# extbrd.net
KiCad netlist of a schematic drawn in EAGLE
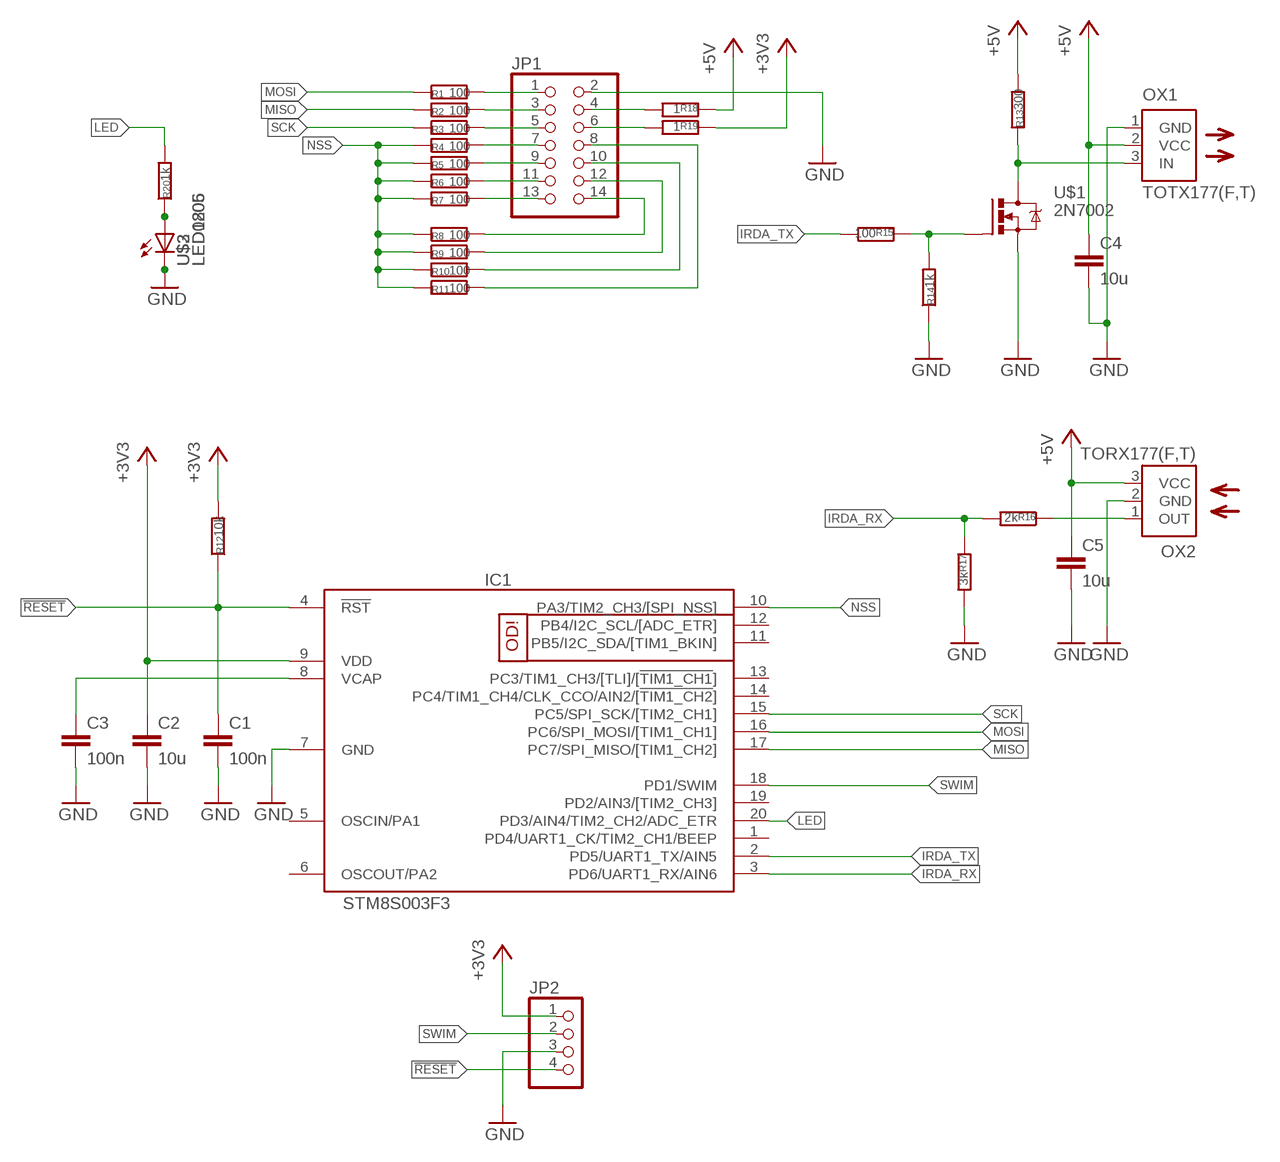
[diagram p0: schematic, sheet 1]

(export (version "E")
  (design (tool "Eeschema 10.0.6"))
  (components
    (comp (ref "C1")
      (value "100n")
      (footprint "eagle-import:C0603")
      (libsource (lib "eagle-import") (part "CC0603"))
    )
    (comp (ref "C2")
      (value "10u")
      (footprint "eagle-import:C0805")
      (libsource (lib "eagle-import") (part "CC0805"))
    )
    (comp (ref "C3")
      (value "100n")
      (footprint "eagle-import:C0603")
      (libsource (lib "eagle-import") (part "CC0603"))
    )
    (comp (ref "C4")
      (value "10u")
      (footprint "eagle-import:C0805")
      (libsource (lib "eagle-import") (part "CC0805"))
    )
    (comp (ref "C5")
      (value "10u")
      (footprint "eagle-import:C0805")
      (libsource (lib "eagle-import") (part "CC0805"))
    )
    (comp (ref "IC1")
      (value "STM8S003F3")
      (footprint "eagle-import:TSSOP20")
      (libsource (lib "eagle-import") (part "STM8S003F3"))
    )
    (comp (ref "JP1")
      (value "PINHD-2X07_2.54-SMD")
      (footprint "eagle-import:2X07SMD")
      (libsource (lib "eagle-import") (part "PINHD-2X07_2.54-SMD"))
    )
    (comp (ref "JP2")
      (value "PINHD-1X04_2.54-SMD")
      (footprint "eagle-import:1X04SMD")
      (libsource (lib "eagle-import") (part "PINHD-1X04_2.54-SMD"))
    )
    (comp (ref "OX1")
      (value "TOTX177(F,T)")
      (footprint "eagle-import:TOTX")
      (libsource (lib "eagle-import") (part "TOTX177(F,T)"))
    )
    (comp (ref "OX2")
      (value "TORX177(F,T)")
      (footprint "eagle-import:TORX")
      (libsource (lib "eagle-import") (part "TORX177(F,T)"))
    )
    (comp (ref "R1")
      (value "100")
      (footprint "eagle-import:0603")
      (libsource (lib "eagle-import") (part "R0603"))
    )
    (comp (ref "R2")
      (value "100")
      (footprint "eagle-import:0603")
      (libsource (lib "eagle-import") (part "R0603"))
    )
    (comp (ref "R3")
      (value "100")
      (footprint "eagle-import:0603")
      (libsource (lib "eagle-import") (part "R0603"))
    )
    (comp (ref "R4")
      (value "100")
      (footprint "eagle-import:0603")
      (libsource (lib "eagle-import") (part "R0603"))
    )
    (comp (ref "R5")
      (value "100")
      (footprint "eagle-import:0603")
      (libsource (lib "eagle-import") (part "R0603"))
    )
    (comp (ref "R6")
      (value "100")
      (footprint "eagle-import:0603")
      (libsource (lib "eagle-import") (part "R0603"))
    )
    (comp (ref "R7")
      (value "100")
      (footprint "eagle-import:0603")
      (libsource (lib "eagle-import") (part "R0603"))
    )
    (comp (ref "R8")
      (value "100")
      (footprint "eagle-import:0603")
      (libsource (lib "eagle-import") (part "R0603"))
    )
    (comp (ref "R9")
      (value "100")
      (footprint "eagle-import:0603")
      (libsource (lib "eagle-import") (part "R0603"))
    )
    (comp (ref "R10")
      (value "100")
      (footprint "eagle-import:0603")
      (libsource (lib "eagle-import") (part "R0603"))
    )
    (comp (ref "R11")
      (value "100")
      (footprint "eagle-import:0603")
      (libsource (lib "eagle-import") (part "R0603"))
    )
    (comp (ref "R12")
      (value "10k")
      (footprint "eagle-import:0603")
      (libsource (lib "eagle-import") (part "R0603"))
    )
    (comp (ref "R13")
      (value "300")
      (footprint "eagle-import:0603")
      (libsource (lib "eagle-import") (part "R0603"))
    )
    (comp (ref "R14")
      (value "1k")
      (footprint "eagle-import:0603")
      (libsource (lib "eagle-import") (part "R0603"))
    )
    (comp (ref "R15")
      (value "100")
      (footprint "eagle-import:0603")
      (libsource (lib "eagle-import") (part "R0603"))
    )
    (comp (ref "R16")
      (value "2k")
      (footprint "eagle-import:0603")
      (libsource (lib "eagle-import") (part "R0603"))
    )
    (comp (ref "R17")
      (value "3k")
      (footprint "eagle-import:0603")
      (libsource (lib "eagle-import") (part "R0603"))
    )
    (comp (ref "R18")
      (value "1")
      (footprint "eagle-import:0603")
      (libsource (lib "eagle-import") (part "R0603"))
    )
    (comp (ref "R19")
      (value "1")
      (footprint "eagle-import:0603")
      (libsource (lib "eagle-import") (part "R0603"))
    )
    (comp (ref "R20")
      (value "1k")
      (footprint "eagle-import:0603")
      (libsource (lib "eagle-import") (part "R0603"))
    )
    (comp (ref "U$1")
      (value "2N7002")
      (footprint "eagle-import:SOT23")
      (libsource (lib "eagle-import") (part "2N7002"))
    )
    (comp (ref "U$2")
      (value "LED0805")
      (footprint "eagle-import:0805-LED")
      (libsource (lib "eagle-import") (part "LED0805"))
    )
    (comp (ref "U$3")
      (value "LED1206")
      (footprint "eagle-import:1206-LED")
      (libsource (lib "eagle-import") (part "LED1206"))
    )
  )
  (nets
    (net (code "1") (name "+3V3") (class "Default")
      (node (ref "C2") (pin "1") (pinfunction "1_1") (pintype "passive"))
      (node (ref "IC1") (pin "9") (pinfunction "VDD_9") (pintype "power_in"))
      (node (ref "JP2") (pin "1") (pinfunction "1_1") (pintype "passive"))
      (node (ref "R12") (pin "2") (pinfunction "2_2") (pintype "passive"))
      (node (ref "R19") (pin "1") (pinfunction "1_1") (pintype "passive"))
    )
    (net (code "2") (name "+5V") (class "Default")
      (node (ref "C4") (pin "1") (pinfunction "1_1") (pintype "passive"))
      (node (ref "C5") (pin "1") (pinfunction "1_1") (pintype "passive"))
      (node (ref "OX1") (pin "2") (pinfunction "VCC_2") (pintype "power_in"))
      (node (ref "OX2") (pin "3") (pinfunction "VCC_3") (pintype "power_in"))
      (node (ref "R13") (pin "2") (pinfunction "2_2") (pintype "passive"))
      (node (ref "R18") (pin "1") (pinfunction "1_1") (pintype "passive"))
    )
    (net (code "3") (name "/~{RESET}") (class "Default")
      (node (ref "C1") (pin "1") (pinfunction "1_1") (pintype "passive"))
      (node (ref "IC1") (pin "4") (pinfunction "~{RST}_4") (pintype "input"))
      (node (ref "JP2") (pin "4") (pinfunction "4_4") (pintype "passive"))
      (node (ref "R12") (pin "1") (pinfunction "1_1") (pintype "passive"))
    )
    (net (code "4") (name "GND") (class "Default")
      (node (ref "C1") (pin "2") (pinfunction "2_2") (pintype "passive"))
      (node (ref "C2") (pin "2") (pinfunction "2_2") (pintype "passive"))
      (node (ref "C3") (pin "2") (pinfunction "2_2") (pintype "passive"))
      (node (ref "C4") (pin "2") (pinfunction "2_2") (pintype "passive"))
      (node (ref "C5") (pin "2") (pinfunction "2_2") (pintype "passive"))
      (node (ref "IC1") (pin "7") (pinfunction "GND_7") (pintype "power_in"))
      (node (ref "JP1") (pin "2") (pinfunction "2_2") (pintype "passive"))
      (node (ref "JP2") (pin "3") (pinfunction "3_3") (pintype "passive"))
      (node (ref "OX1") (pin "1") (pinfunction "GND_1") (pintype "power_in"))
      (node (ref "OX2") (pin "2") (pinfunction "GND_2") (pintype "power_in"))
      (node (ref "R14") (pin "1") (pinfunction "1_1") (pintype "passive"))
      (node (ref "R17") (pin "2") (pinfunction "2_2") (pintype "passive"))
      (node (ref "U$1") (pin "2") (pinfunction "S_2") (pintype "passive"))
      (node (ref "U$2") (pin "C") (pinfunction "C_C") (pintype "passive"))
      (node (ref "U$3") (pin "C") (pinfunction "C_C") (pintype "passive"))
    )
    (net (code "5") (name "IRDA_RX") (class "Default")
      (node (ref "IC1") (pin "3") (pinfunction "PD6/UART1_RX/AIN6_3") (pintype "bidirectional"))
      (node (ref "R16") (pin "2") (pinfunction "2_2") (pintype "passive"))
      (node (ref "R17") (pin "1") (pinfunction "1_1") (pintype "passive"))
    )
    (net (code "6") (name "IRDA_TX") (class "Default")
      (node (ref "IC1") (pin "2") (pinfunction "PD5/UART1_TX/AIN5_2") (pintype "bidirectional"))
      (node (ref "R15") (pin "2") (pinfunction "2_2") (pintype "passive"))
    )
    (net (code "7") (name "LED") (class "Default")
      (node (ref "IC1") (pin "20") (pinfunction "PD3/AIN4/TIM2_CH2/ADC_ETR_20") (pintype "bidirectional"))
      (node (ref "R20") (pin "2") (pinfunction "2_2") (pintype "passive"))
    )
    (net (code "8") (name "MISO") (class "Default")
      (node (ref "IC1") (pin "17") (pinfunction "PC7/SPI_MISO/[TIM1_CH2]_17") (pintype "bidirectional"))
      (node (ref "R2") (pin "1") (pinfunction "1_1") (pintype "passive"))
    )
    (net (code "9") (name "MOSI") (class "Default")
      (node (ref "IC1") (pin "16") (pinfunction "PC6/SPI_MOSI/[TIM1_CH1]_16") (pintype "bidirectional"))
      (node (ref "R1") (pin "1") (pinfunction "1_1") (pintype "passive"))
    )
    (net (code "10") (name "NSS") (class "Default")
      (node (ref "IC1") (pin "10") (pinfunction "PA3/TIM2_CH3/[SPI_NSS]_10") (pintype "bidirectional"))
      (node (ref "R10") (pin "1") (pinfunction "1_1") (pintype "passive"))
      (node (ref "R11") (pin "1") (pinfunction "1_1") (pintype "passive"))
      (node (ref "R4") (pin "1") (pinfunction "1_1") (pintype "passive"))
      (node (ref "R5") (pin "1") (pinfunction "1_1") (pintype "passive"))
      (node (ref "R6") (pin "1") (pinfunction "1_1") (pintype "passive"))
      (node (ref "R7") (pin "1") (pinfunction "1_1") (pintype "passive"))
      (node (ref "R8") (pin "1") (pinfunction "1_1") (pintype "passive"))
      (node (ref "R9") (pin "1") (pinfunction "1_1") (pintype "passive"))
    )
    (net (code "11") (name "Net-(IC1-VCAP)") (class "Default")
      (node (ref "C3") (pin "1") (pinfunction "1_1") (pintype "passive"))
      (node (ref "IC1") (pin "8") (pinfunction "VCAP_8") (pintype "power_in"))
    )
    (net (code "12") (name "Net-(JP1-Pad1)") (class "Default")
      (node (ref "JP1") (pin "1") (pinfunction "1_1") (pintype "passive"))
      (node (ref "R1") (pin "2") (pinfunction "2_2") (pintype "passive"))
    )
    (net (code "13") (name "Net-(JP1-Pad3)") (class "Default")
      (node (ref "JP1") (pin "3") (pinfunction "3_3") (pintype "passive"))
      (node (ref "R2") (pin "2") (pinfunction "2_2") (pintype "passive"))
    )
    (net (code "14") (name "Net-(JP1-Pad4)") (class "Default")
      (node (ref "JP1") (pin "4") (pinfunction "4_4") (pintype "passive"))
      (node (ref "R18") (pin "2") (pinfunction "2_2") (pintype "passive"))
    )
    (net (code "15") (name "Net-(JP1-Pad5)") (class "Default")
      (node (ref "JP1") (pin "5") (pinfunction "5_5") (pintype "passive"))
      (node (ref "R3") (pin "2") (pinfunction "2_2") (pintype "passive"))
    )
    (net (code "16") (name "Net-(JP1-Pad6)") (class "Default")
      (node (ref "JP1") (pin "6") (pinfunction "6_6") (pintype "passive"))
      (node (ref "R19") (pin "2") (pinfunction "2_2") (pintype "passive"))
    )
    (net (code "17") (name "Net-(JP1-Pad7)") (class "Default")
      (node (ref "JP1") (pin "7") (pinfunction "7_7") (pintype "passive"))
      (node (ref "R4") (pin "2") (pinfunction "2_2") (pintype "passive"))
    )
    (net (code "18") (name "Net-(JP1-Pad8)") (class "Default")
      (node (ref "JP1") (pin "8") (pinfunction "8_8") (pintype "passive"))
      (node (ref "R11") (pin "2") (pinfunction "2_2") (pintype "passive"))
    )
    (net (code "19") (name "Net-(JP1-Pad9)") (class "Default")
      (node (ref "JP1") (pin "9") (pinfunction "9_9") (pintype "passive"))
      (node (ref "R5") (pin "2") (pinfunction "2_2") (pintype "passive"))
    )
    (net (code "20") (name "Net-(JP1-Pad10)") (class "Default")
      (node (ref "JP1") (pin "10") (pinfunction "10_10") (pintype "passive"))
      (node (ref "R10") (pin "2") (pinfunction "2_2") (pintype "passive"))
    )
    (net (code "21") (name "Net-(JP1-Pad11)") (class "Default")
      (node (ref "JP1") (pin "11") (pinfunction "11_11") (pintype "passive"))
      (node (ref "R6") (pin "2") (pinfunction "2_2") (pintype "passive"))
    )
    (net (code "22") (name "Net-(JP1-Pad12)") (class "Default")
      (node (ref "JP1") (pin "12") (pinfunction "12_12") (pintype "passive"))
      (node (ref "R9") (pin "2") (pinfunction "2_2") (pintype "passive"))
    )
    (net (code "23") (name "Net-(JP1-Pad13)") (class "Default")
      (node (ref "JP1") (pin "13") (pinfunction "13_13") (pintype "passive"))
      (node (ref "R7") (pin "2") (pinfunction "2_2") (pintype "passive"))
    )
    (net (code "24") (name "Net-(JP1-Pad14)") (class "Default")
      (node (ref "JP1") (pin "14") (pinfunction "14_14") (pintype "passive"))
      (node (ref "R8") (pin "2") (pinfunction "2_2") (pintype "passive"))
    )
    (net (code "25") (name "Net-(OX1-IN)") (class "Default")
      (node (ref "OX1") (pin "3") (pinfunction "IN_3") (pintype "input"))
      (node (ref "R13") (pin "1") (pinfunction "1_1") (pintype "passive"))
      (node (ref "U$1") (pin "3") (pinfunction "D_3") (pintype "passive"))
    )
    (net (code "26") (name "Net-(OX2-OUT)") (class "Default")
      (node (ref "OX2") (pin "1") (pinfunction "OUT_1") (pintype "output"))
      (node (ref "R16") (pin "1") (pinfunction "1_1") (pintype "passive"))
    )
    (net (code "27") (name "Net-(R20-Pad1)") (class "Default")
      (node (ref "R20") (pin "1") (pinfunction "1_1") (pintype "passive"))
      (node (ref "U$2") (pin "A") (pinfunction "A_A") (pintype "passive"))
      (node (ref "U$3") (pin "A") (pinfunction "A_A") (pintype "passive"))
    )
    (net (code "28") (name "Net-(U$1-G)") (class "Default")
      (node (ref "R14") (pin "2") (pinfunction "2_2") (pintype "passive"))
      (node (ref "R15") (pin "1") (pinfunction "1_1") (pintype "passive"))
      (node (ref "U$1") (pin "1") (pinfunction "G_1") (pintype "passive"))
    )
    (net (code "29") (name "SCK") (class "Default")
      (node (ref "IC1") (pin "15") (pinfunction "PC5/SPI_SCK/[TIM2_CH1]_15") (pintype "bidirectional"))
      (node (ref "R3") (pin "1") (pinfunction "1_1") (pintype "passive"))
    )
    (net (code "30") (name "SWIM") (class "Default")
      (node (ref "IC1") (pin "18") (pinfunction "PD1/SWIM_18") (pintype "bidirectional"))
      (node (ref "JP2") (pin "2") (pinfunction "2_2") (pintype "passive"))
    )
    (net (code "31") (name "unconnected-(IC1-OSCIN{slash}PA1-Pad5)") (class "Default")
      (node (ref "IC1") (pin "5") (pinfunction "OSCIN/PA1_5") (pintype "bidirectional"))
    )
    (net (code "32") (name "unconnected-(IC1-OSCOUT{slash}PA2-Pad6)") (class "Default")
      (node (ref "IC1") (pin "6") (pinfunction "OSCOUT/PA2_6") (pintype "bidirectional"))
    )
    (net (code "33") (name "unconnected-(IC1-PB4{slash}I2C_SCL{slash}[ADC_ETR]-Pad12)") (class "Default")
      (node (ref "IC1") (pin "12") (pinfunction "PB4/I2C_SCL/[ADC_ETR]_12") (pintype "bidirectional"))
    )
    (net (code "34") (name "unconnected-(IC1-PB5{slash}I2C_SDA{slash}[TIM1_BKIN]-Pad11)") (class "Default")
      (node (ref "IC1") (pin "11") (pinfunction "PB5/I2C_SDA/[TIM1_BKIN]_11") (pintype "bidirectional"))
    )
    (net (code "35") (name "unconnected-(IC1-PC3{slash}TIM1_CH3{slash}[TLI]{slash}[~{TIM1_CH1}]-Pad13)") (class "Default")
      (node (ref "IC1") (pin "13") (pinfunction "PC3/TIM1_CH3/[TLI]/[~{TIM1_CH1}]_13") (pintype "bidirectional"))
    )
    (net (code "36") (name "unconnected-(IC1-PC4{slash}TIM1_CH4{slash}CLK_CCO{slash}AIN2{slash}[~{TIM1_CH2}]-Pad14)") (class "Default")
      (node (ref "IC1") (pin "14") (pinfunction "PC4/TIM1_CH4/CLK_CCO/AIN2/[~{TIM1_CH2}]_14") (pintype "bidirectional"))
    )
    (net (code "37") (name "unconnected-(IC1-PD2{slash}AIN3{slash}[TIM2_CH3]-Pad19)") (class "Default")
      (node (ref "IC1") (pin "19") (pinfunction "PD2/AIN3/[TIM2_CH3]_19") (pintype "bidirectional"))
    )
    (net (code "38") (name "unconnected-(IC1-PD4{slash}UART1_CK{slash}TIM2_CH1{slash}BEEP-Pad1)") (class "Default")
      (node (ref "IC1") (pin "1") (pinfunction "PD4/UART1_CK/TIM2_CH1/BEEP_1") (pintype "bidirectional"))
    )
  )
)
